# SAMD21_Pro_RF_1W.net
KiCad netlist of a schematic drawn in EAGLE
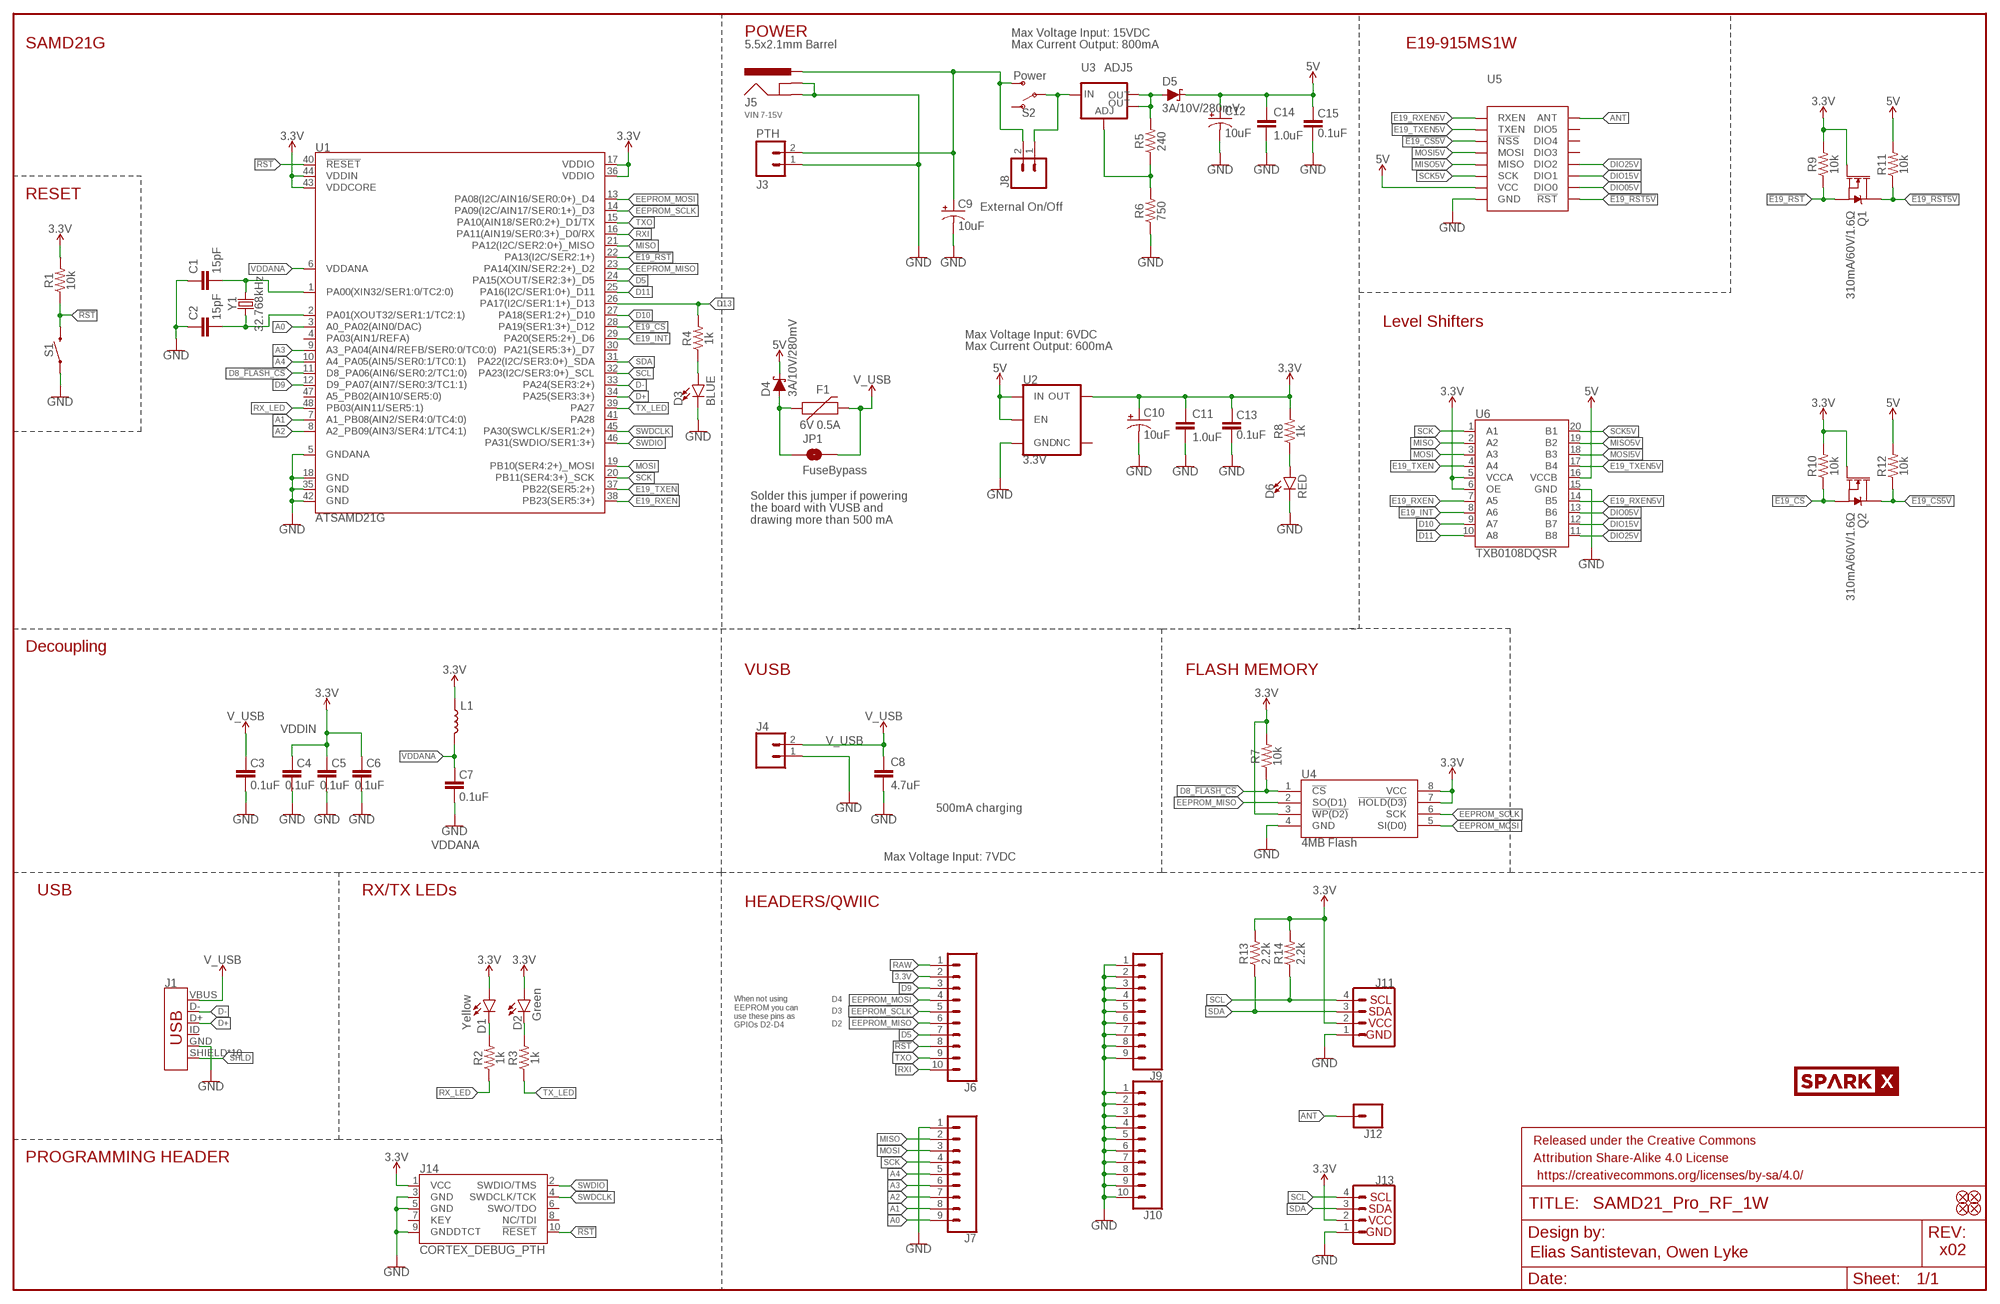
[diagram p0: schematic, sheet 1]

(export (version "E")
  (design (tool "Eeschema 10.0.6"))
  (components
    (comp (ref "C1")
      (value "15pF")
      (footprint "eagle-import:0603")
      (libsource (lib "eagle-import") (part "15PF-0603-50V-5%"))
    )
    (comp (ref "C2")
      (value "15pF")
      (footprint "eagle-import:0603")
      (libsource (lib "eagle-import") (part "15PF-0603-50V-5%"))
    )
    (comp (ref "C3")
      (value "0.1uF")
      (footprint "eagle-import:0603")
      (libsource (lib "eagle-import") (part "0.1UF-0603-25V-(+80/-20%)"))
    )
    (comp (ref "C4")
      (value "0.1uF")
      (footprint "eagle-import:0603")
      (libsource (lib "eagle-import") (part "0.1UF-0603-25V-(+80/-20%)"))
    )
    (comp (ref "C5")
      (value "0.1uF")
      (footprint "eagle-import:0603")
      (libsource (lib "eagle-import") (part "0.1UF-0603-25V-(+80/-20%)"))
    )
    (comp (ref "C6")
      (value "0.1uF")
      (footprint "eagle-import:0603")
      (libsource (lib "eagle-import") (part "0.1UF-0603-25V-(+80/-20%)"))
    )
    (comp (ref "C7")
      (value "0.1uF")
      (footprint "eagle-import:0603")
      (libsource (lib "eagle-import") (part "0.1UF-0603-25V-(+80/-20%)"))
    )
    (comp (ref "C8")
      (value "4.7uF")
      (footprint "eagle-import:0603")
      (libsource (lib "eagle-import") (part "4.7UF-0603-6.3V-(10%)"))
    )
    (comp (ref "C9")
      (value "10uF")
      (footprint "eagle-import:EIA3216")
      (libsource (lib "eagle-import") (part "10UF-POLAR-EIA3216-16V-10%(TANT)"))
    )
    (comp (ref "C10")
      (value "10uF")
      (footprint "eagle-import:EIA3216")
      (libsource (lib "eagle-import") (part "10UF-POLAR-EIA3216-16V-10%(TANT)"))
    )
    (comp (ref "C11")
      (value "1.0uF")
      (footprint "eagle-import:0603")
      (libsource (lib "eagle-import") (part "1.0UF-0603-16V-10%"))
    )
    (comp (ref "C12")
      (value "10uF")
      (footprint "eagle-import:EIA3216")
      (libsource (lib "eagle-import") (part "10UF-POLAR-EIA3216-16V-10%(TANT)"))
    )
    (comp (ref "C13")
      (value "0.1uF")
      (footprint "eagle-import:0603")
      (libsource (lib "eagle-import") (part "0.1UF-0603-25V-(+80/-20%)"))
    )
    (comp (ref "C14")
      (value "1.0uF")
      (footprint "eagle-import:0603")
      (libsource (lib "eagle-import") (part "1.0UF-0603-16V-10%"))
    )
    (comp (ref "C15")
      (value "0.1uF")
      (footprint "eagle-import:0603")
      (libsource (lib "eagle-import") (part "0.1UF-0603-25V-(+80/-20%)"))
    )
    (comp (ref "D1")
      (value "Yellow")
      (footprint "eagle-import:LED-0603")
      (libsource (lib "eagle-import") (part "LED-YELLOW0603"))
    )
    (comp (ref "D2")
      (value "Green")
      (footprint "eagle-import:LED-0603")
      (libsource (lib "eagle-import") (part "LED-GREEN0603"))
    )
    (comp (ref "D3")
      (value "BLUE")
      (footprint "eagle-import:LED-0603")
      (libsource (lib "eagle-import") (part "LED-BLUE0603"))
    )
    (comp (ref "D4")
      (value "3A/10V/280mV")
      (footprint "eagle-import:SOD-323")
      (libsource (lib "eagle-import") (part "DIODE-SCHOTTKY-BAT60A"))
    )
    (comp (ref "D5")
      (value "3A/10V/280mV")
      (footprint "eagle-import:SOD-323")
      (libsource (lib "eagle-import") (part "DIODE-SCHOTTKY-BAT60A"))
    )
    (comp (ref "D6")
      (value "RED")
      (footprint "eagle-import:LED-0603")
      (libsource (lib "eagle-import") (part "LED-RED0603"))
    )
    (comp (ref "F1")
      (value "6V 0.5A")
      (footprint "eagle-import:0805")
      (libsource (lib "eagle-import") (part "PPTC_6V500MA"))
    )
    (comp (ref "FD1")
      (value "FIDUCIAL1X2")
      (footprint "eagle-import:FIDUCIAL-1X2")
      (libsource (lib "eagle-import") (part "FIDUCIAL1X2"))
    )
    (comp (ref "FD2")
      (value "FIDUCIAL1X2")
      (footprint "eagle-import:FIDUCIAL-1X2")
      (libsource (lib "eagle-import") (part "FIDUCIAL1X2"))
    )
    (comp (ref "FD3")
      (value "FIDUCIAL1X2")
      (footprint "eagle-import:FIDUCIAL-1X2")
      (libsource (lib "eagle-import") (part "FIDUCIAL1X2"))
    )
    (comp (ref "FD4")
      (value "FIDUCIAL1X2")
      (footprint "eagle-import:FIDUCIAL-1X2")
      (libsource (lib "eagle-import") (part "FIDUCIAL1X2"))
    )
    (comp (ref "FRAME1")
      (value "FRAME-LEDGER")
      (footprint "eagle-import:CREATIVE_COMMONS")
      (libsource (lib "eagle-import") (part "FRAME-LEDGER"))
    )
    (comp (ref "J1")
      (value "USB_MICRO-B_HALF_PTH_MILL")
      (footprint "eagle-import:USB-MICROB-PTH-MILL")
      (libsource (lib "eagle-import") (part "USB_MICRO-B_HALF_PTH_MILL"))
    )
    (comp (ref "J3")
      (value "PTH")
      (footprint "eagle-import:1X02_NO_SILK")
      (libsource (lib "eagle-import") (part "CONN_021X02_NO_SILK"))
    )
    (comp (ref "J4")
      (value "CONN_021X02_NO_SILK")
      (footprint "eagle-import:1X02_NO_SILK")
      (libsource (lib "eagle-import") (part "CONN_021X02_NO_SILK"))
    )
    (comp (ref "J5")
      (value "5.5x2.1mm Barrel")
      (footprint "eagle-import:POWER_JACK_SMD")
      (libsource (lib "eagle-import") (part "POWER_JACKSMD"))
    )
    (comp (ref "J6")
      (value "CONN_10NO_SILK_PTH_FEMALE")
      (footprint "eagle-import:1X10_NO_SILK")
      (libsource (lib "eagle-import") (part "CONN_10NO_SILK_PTH_FEMALE"))
    )
    (comp (ref "J7")
      (value "CONN_09NO_SILK")
      (footprint "eagle-import:1X09_NO_SILK")
      (libsource (lib "eagle-import") (part "CONN_09NO_SILK"))
    )
    (comp (ref "J8")
      (value "External On/Off")
      (footprint "eagle-import:1X02_NO_SILK")
      (libsource (lib "eagle-import") (part "CONN_021X02_NO_SILK"))
    )
    (comp (ref "J9")
      (value "CONN_09NO_SILK")
      (footprint "eagle-import:1X09_NO_SILK")
      (libsource (lib "eagle-import") (part "CONN_09NO_SILK"))
    )
    (comp (ref "J10")
      (value "CONN_10NO_SILK_PTH_FEMALE")
      (footprint "eagle-import:1X10_NO_SILK")
      (libsource (lib "eagle-import") (part "CONN_10NO_SILK_PTH_FEMALE"))
    )
    (comp (ref "J11")
      (value "QWIIC_CONNECTORJS-1MM")
      (footprint "eagle-import:1X04_1MM_RA")
      (libsource (lib "eagle-import") (part "QWIIC_CONNECTORJS-1MM"))
    )
    (comp (ref "J12")
      (value "CONN_01PTH_NO_SILK_YES_STOP")
      (footprint "eagle-import:1X01_NO_SILK")
      (libsource (lib "eagle-import") (part "CONN_01PTH_NO_SILK_YES_STOP"))
    )
    (comp (ref "J13")
      (value "QWIIC_CONNECTORJS-1MM")
      (footprint "eagle-import:1X04_1MM_RA")
      (libsource (lib "eagle-import") (part "QWIIC_CONNECTORJS-1MM"))
    )
    (comp (ref "J14")
      (value "CORTEX_DEBUG_PTH")
      (footprint "eagle-import:2X5-PTH-1.27MM")
      (libsource (lib "eagle-import") (part "CORTEX_DEBUG_PTH"))
    )
    (comp (ref "JP1")
      (value "FuseBypass")
      (footprint "eagle-import:SMT-JUMPER_2_NO_SILK")
      (libsource (lib "eagle-import") (part "JUMPER-SMT_2_NO_SILK"))
    )
    (comp (ref "L1")
      (value "INDUCTORFB-30OHM")
      (footprint "eagle-import:0603")
      (libsource (lib "eagle-import") (part "INDUCTORFB-30OHM"))
    )
    (comp (ref "Q1")
      (value "310mA/60V/1.6Ω")
      (footprint "eagle-import:SOT323")
      (libsource (lib "eagle-import") (part "MOSFET-NCH-2N7002PW"))
    )
    (comp (ref "Q2")
      (value "310mA/60V/1.6Ω")
      (footprint "eagle-import:SOT323")
      (libsource (lib "eagle-import") (part "MOSFET-NCH-2N7002PW"))
    )
    (comp (ref "R1")
      (value "10k")
      (footprint "eagle-import:0603")
      (libsource (lib "eagle-import") (part "10KOHM-0603-1/10W-1%"))
    )
    (comp (ref "R2")
      (value "1k")
      (footprint "eagle-import:0603")
      (libsource (lib "eagle-import") (part "1KOHM-0603-1/10W-1%"))
    )
    (comp (ref "R3")
      (value "1k")
      (footprint "eagle-import:0603")
      (libsource (lib "eagle-import") (part "1KOHM-0603-1/10W-1%"))
    )
    (comp (ref "R4")
      (value "1k")
      (footprint "eagle-import:0603")
      (libsource (lib "eagle-import") (part "1KOHM-0603-1/10W-1%"))
    )
    (comp (ref "R5")
      (value "240")
      (footprint "eagle-import:0603")
      (libsource (lib "eagle-import") (part "240OHM-0603-1/10W-1%"))
    )
    (comp (ref "R6")
      (value "750")
      (footprint "eagle-import:0603")
      (libsource (lib "eagle-import") (part "750OHM-0603-1/10W-1%"))
    )
    (comp (ref "R7")
      (value "10k")
      (footprint "eagle-import:0603")
      (libsource (lib "eagle-import") (part "10KOHM-0603-1/10W-1%"))
    )
    (comp (ref "R8")
      (value "1k")
      (footprint "eagle-import:0603")
      (libsource (lib "eagle-import") (part "1KOHM-0603-1/10W-1%"))
    )
    (comp (ref "R9")
      (value "10k")
      (footprint "eagle-import:0603")
      (libsource (lib "eagle-import") (part "10KOHM-0603-1/10W-1%"))
    )
    (comp (ref "R10")
      (value "10k")
      (footprint "eagle-import:0603")
      (libsource (lib "eagle-import") (part "10KOHM-0603-1/10W-1%"))
    )
    (comp (ref "R11")
      (value "10k")
      (footprint "eagle-import:0603")
      (libsource (lib "eagle-import") (part "10KOHM-0603-1/10W-1%"))
    )
    (comp (ref "R12")
      (value "10k")
      (footprint "eagle-import:0603")
      (libsource (lib "eagle-import") (part "10KOHM-0603-1/10W-1%"))
    )
    (comp (ref "R13")
      (value "2.2k")
      (footprint "eagle-import:0603")
      (libsource (lib "eagle-import") (part "2.2KOHM-0603-1/10W-1%"))
    )
    (comp (ref "R14")
      (value "2.2k")
      (footprint "eagle-import:0603")
      (libsource (lib "eagle-import") (part "2.2KOHM-0603-1/10W-1%"))
    )
    (comp (ref "S1")
      (value "MOMENTARY-SWITCH-SPST-SMD-5.2-REDUNDANT")
      (footprint "eagle-import:TACTILE_SWITCH_SMD_5.2MM")
      (libsource (lib "eagle-import") (part "MOMENTARY-SWITCH-SPST-SMD-5.2-REDUNDANT"))
    )
    (comp (ref "S2")
      (value "Power")
      (footprint "eagle-import:SWITCH_SPST_SMD_A")
      (libsource (lib "eagle-import") (part "SWITCH-SPDT-SMD-RIGHT-ANGLE"))
    )
    (comp (ref "U$34")
      (value "SPARKX-LOGO4")
      (footprint "eagle-import:SPARKX-MEDIUM")
      (libsource (lib "eagle-import") (part "SPARKX-LOGO4"))
    )
    (comp (ref "U1")
      (value "ATSAMD21G")
      (footprint "eagle-import:QFN-48_NO_EXPOSED_PAD")
      (libsource (lib "eagle-import") (part "ATSAMD21G"))
    )
    (comp (ref "U2")
      (value "3.3V")
      (footprint "eagle-import:SOT23-5")
      (libsource (lib "eagle-import") (part "V_REG_AP2112K-3.3V"))
    )
    (comp (ref "U3")
      (value "ADJ5")
      (footprint "eagle-import:SOT223")
      (libsource (lib "eagle-import") (part "V_REG_LM1117SOT223"))
    )
    (comp (ref "U4")
      (value "4MB Flash")
      (footprint "eagle-import:SO08")
      (libsource (lib "eagle-import") (part "AT25SF041"))
    )
    (comp (ref "U5")
      (value "E19-915MS1W")
      (footprint "eagle-import:E19-915MS1W")
      (libsource (lib "eagle-import") (part "E19-915MS1W"))
    )
    (comp (ref "U6")
      (value "TXB0108DQSR")
      (footprint "eagle-import:UFDFN-20")
      (libsource (lib "eagle-import") (part "TXB0108"))
    )
    (comp (ref "Y1")
      (value "32.768kHz")
      (footprint "eagle-import:CRYSTAL-SMD-3.2X1.5MM")
      (libsource (lib "eagle-import") (part "CRYSTAL-32.768KHZSMD-3.2X1.5"))
    )
  )
  (nets
    (net (code "1") (name "/D8_~{FLASH_CS}") (class "Default")
      (node (ref "R7") (pin "1") (pinfunction "1_1") (pintype "passive"))
      (node (ref "U1") (pin "11") (pinfunction "D8_PA06(AIN6/SER0:2/TC1:0)_11") (pintype "bidirectional"))
      (node (ref "U4") (pin "1") (pinfunction "~{CS}_1") (pintype "bidirectional"))
    )
    (net (code "2") (name "/~{E19_CS5V}") (class "Default")
      (node (ref "Q2") (pin "3") (pinfunction "D_3") (pintype "bidirectional"))
      (node (ref "R12") (pin "1") (pinfunction "1_1") (pintype "passive"))
      (node (ref "U5") (pin "P$15") (pinfunction "~{NSS}_P$15") (pintype "bidirectional"))
    )
    (net (code "3") (name "/~{E19_CS}") (class "Default")
      (node (ref "Q2") (pin "2") (pinfunction "S_2") (pintype "bidirectional"))
      (node (ref "R10") (pin "1") (pinfunction "1_1") (pintype "passive"))
      (node (ref "U1") (pin "28") (pinfunction "PA19(SER1:3+)_D12_28") (pintype "bidirectional"))
    )
    (net (code "4") (name "/~{E19_RST5V}") (class "Default")
      (node (ref "Q1") (pin "3") (pinfunction "D_3") (pintype "bidirectional"))
      (node (ref "R11") (pin "1") (pinfunction "1_1") (pintype "passive"))
      (node (ref "U5") (pin "P$8") (pinfunction "~{RST}_P$8") (pintype "bidirectional"))
    )
    (net (code "5") (name "/~{E19_RST}") (class "Default")
      (node (ref "Q1") (pin "2") (pinfunction "S_2") (pintype "bidirectional"))
      (node (ref "R9") (pin "1") (pinfunction "1_1") (pintype "passive"))
      (node (ref "U1") (pin "22") (pinfunction "PA13(I2C/SER2:1+)_22") (pintype "bidirectional"))
    )
    (net (code "6") (name "/~{RST}") (class "Default")
      (node (ref "J14") (pin "10") (pinfunction "~{RESET}_10") (pintype "bidirectional"))
      (node (ref "J6") (pin "8") (pinfunction "8_8") (pintype "passive"))
      (node (ref "R1") (pin "1") (pinfunction "1_1") (pintype "passive"))
      (node (ref "S1") (pin "3") (pinfunction "2_3") (pintype "passive"))
      (node (ref "S1") (pin "4") (pinfunction "2_4") (pintype "passive"))
      (node (ref "U1") (pin "40") (pinfunction "~{RESET}_40") (pintype "bidirectional"))
    )
    (net (code "7") (name "3.3V") (class "Default")
      (node (ref "C10") (pin "+") (pinfunction "+_+") (pintype "passive"))
      (node (ref "C11") (pin "1") (pinfunction "1_1") (pintype "passive"))
      (node (ref "C13") (pin "2") (pinfunction "2_2") (pintype "passive"))
      (node (ref "C4") (pin "2") (pinfunction "2_2") (pintype "passive"))
      (node (ref "C5") (pin "2") (pinfunction "2_2") (pintype "passive"))
      (node (ref "C6") (pin "2") (pinfunction "2_2") (pintype "passive"))
      (node (ref "D1") (pin "A") (pinfunction "A_A") (pintype "passive"))
      (node (ref "D2") (pin "A") (pinfunction "A_A") (pintype "passive"))
      (node (ref "J11") (pin "2") (pinfunction "2_2") (pintype "power_in"))
      (node (ref "J13") (pin "2") (pinfunction "2_2") (pintype "power_in"))
      (node (ref "J14") (pin "1") (pinfunction "VCC_1") (pintype "bidirectional"))
      (node (ref "J6") (pin "2") (pinfunction "2_2") (pintype "passive"))
      (node (ref "L1") (pin "1") (pinfunction "1_1") (pintype "passive"))
      (node (ref "Q1") (pin "1") (pinfunction "G_1") (pintype "bidirectional"))
      (node (ref "Q2") (pin "1") (pinfunction "G_1") (pintype "bidirectional"))
      (node (ref "R1") (pin "2") (pinfunction "2_2") (pintype "passive"))
      (node (ref "R10") (pin "2") (pinfunction "2_2") (pintype "passive"))
      (node (ref "R13") (pin "2") (pinfunction "2_2") (pintype "passive"))
      (node (ref "R14") (pin "2") (pinfunction "2_2") (pintype "passive"))
      (node (ref "R7") (pin "2") (pinfunction "2_2") (pintype "passive"))
      (node (ref "R8") (pin "2") (pinfunction "2_2") (pintype "passive"))
      (node (ref "R9") (pin "2") (pinfunction "2_2") (pintype "passive"))
      (node (ref "U1") (pin "17") (pinfunction "VDDIO_17") (pintype "bidirectional"))
      (node (ref "U1") (pin "36") (pinfunction "VDDIO_36") (pintype "bidirectional"))
      (node (ref "U1") (pin "43") (pinfunction "VDDCORE_43") (pintype "bidirectional"))
      (node (ref "U1") (pin "44") (pinfunction "VDDIN_44") (pintype "bidirectional"))
      (node (ref "U2") (pin "5") (pinfunction "OUT_5") (pintype "passive"))
      (node (ref "U4") (pin "3") (pinfunction "~{WP(D2})_3") (pintype "bidirectional"))
      (node (ref "U4") (pin "7") (pinfunction "~{HOLD(D3})_7") (pintype "bidirectional"))
      (node (ref "U4") (pin "8") (pinfunction "VCC_8") (pintype "bidirectional"))
      (node (ref "U6") (pin "5") (pinfunction "VCCA_5") (pintype "bidirectional"))
      (node (ref "U6") (pin "6") (pinfunction "OE_6") (pintype "bidirectional"))
    )
    (net (code "8") (name "5V") (class "Default")
      (node (ref "C12") (pin "+") (pinfunction "+_+") (pintype "passive"))
      (node (ref "C14") (pin "1") (pinfunction "1_1") (pintype "passive"))
      (node (ref "C15") (pin "2") (pinfunction "2_2") (pintype "passive"))
      (node (ref "D4") (pin "C") (pinfunction "C_C") (pintype "passive"))
      (node (ref "D5") (pin "C") (pinfunction "C_C") (pintype "passive"))
      (node (ref "R11") (pin "2") (pinfunction "2_2") (pintype "passive"))
      (node (ref "R12") (pin "2") (pinfunction "2_2") (pintype "passive"))
      (node (ref "U2") (pin "1") (pinfunction "IN_1") (pintype "input"))
      (node (ref "U2") (pin "3") (pinfunction "EN_3") (pintype "input"))
      (node (ref "U5") (pin "P$11") (pinfunction "VCC_P$11") (pintype "bidirectional"))
      (node (ref "U6") (pin "16") (pinfunction "VCCB_16") (pintype "bidirectional"))
    )
    (net (code "9") (name "A0") (class "Default")
      (node (ref "J7") (pin "9") (pinfunction "9_9") (pintype "passive"))
      (node (ref "U1") (pin "3") (pinfunction "A0_PA02(AIN0/DAC)_3") (pintype "bidirectional"))
    )
    (net (code "10") (name "A1") (class "Default")
      (node (ref "J7") (pin "8") (pinfunction "8_8") (pintype "passive"))
      (node (ref "U1") (pin "7") (pinfunction "A1_PB08(AIN2/SER4:0/TC4:0)_7") (pintype "bidirectional"))
    )
    (net (code "11") (name "A2") (class "Default")
      (node (ref "J7") (pin "7") (pinfunction "7_7") (pintype "passive"))
      (node (ref "U1") (pin "8") (pinfunction "A2_PB09(AIN3/SER4:1/TC4:1)_8") (pintype "bidirectional"))
    )
    (net (code "12") (name "A3") (class "Default")
      (node (ref "J7") (pin "6") (pinfunction "6_6") (pintype "passive"))
      (node (ref "U1") (pin "9") (pinfunction "A3_PA04(AIN4/REFB/SER0:0/TC0:0)_9") (pintype "bidirectional"))
    )
    (net (code "13") (name "A4") (class "Default")
      (node (ref "J7") (pin "5") (pinfunction "5_5") (pintype "passive"))
      (node (ref "U1") (pin "10") (pinfunction "A4_PA05(AIN5/SER0:1/TC0:1)_10") (pintype "bidirectional"))
    )
    (net (code "14") (name "ANT") (class "Default")
      (node (ref "J12") (pin "1") (pinfunction "1_1") (pintype "passive"))
      (node (ref "U5") (pin "P$19") (pinfunction "ANT_P$19") (pintype "bidirectional"))
    )
    (net (code "15") (name "D+") (class "Default")
      (node (ref "J1") (pin "D+") (pinfunction "D+_D+") (pintype "bidirectional"))
      (node (ref "U1") (pin "34") (pinfunction "PA25(SER3:3+)_34") (pintype "bidirectional"))
    )
    (net (code "16") (name "D-") (class "Default")
      (node (ref "J1") (pin "D-") (pinfunction "D-_D-") (pintype "bidirectional"))
      (node (ref "U1") (pin "33") (pinfunction "PA24(SER3:2+)_33") (pintype "bidirectional"))
    )
    (net (code "17") (name "D5") (class "Default")
      (node (ref "J6") (pin "7") (pinfunction "7_7") (pintype "passive"))
      (node (ref "U1") (pin "24") (pinfunction "PA15(XOUT/SER2:3+)_D5_24") (pintype "bidirectional"))
    )
    (net (code "18") (name "D9") (class "Default")
      (node (ref "J6") (pin "3") (pinfunction "3_3") (pintype "passive"))
      (node (ref "U1") (pin "12") (pinfunction "D9_PA07(AIN7/SER0:3/TC1:1)_12") (pintype "bidirectional"))
    )
    (net (code "19") (name "D10") (class "Default")
      (node (ref "U1") (pin "27") (pinfunction "PA18(SER1:2+)_D10_27") (pintype "bidirectional"))
      (node (ref "U6") (pin "9") (pinfunction "A7_9") (pintype "bidirectional"))
    )
    (net (code "20") (name "D11") (class "Default")
      (node (ref "U1") (pin "25") (pinfunction "PA16(I2C/SER1:0+)_D11_25") (pintype "bidirectional"))
      (node (ref "U6") (pin "10") (pinfunction "A8_10") (pintype "bidirectional"))
    )
    (net (code "21") (name "D13") (class "Default")
      (node (ref "R4") (pin "2") (pinfunction "2_2") (pintype "passive"))
      (node (ref "U1") (pin "26") (pinfunction "PA17(I2C/SER1:1+)_D13_26") (pintype "bidirectional"))
    )
    (net (code "22") (name "DIO05V") (class "Default")
      (node (ref "U5") (pin "P$7") (pinfunction "DIO0_P$7") (pintype "bidirectional"))
      (node (ref "U6") (pin "13") (pinfunction "B6_13") (pintype "bidirectional"))
    )
    (net (code "23") (name "DIO15V") (class "Default")
      (node (ref "U5") (pin "P$6") (pinfunction "DIO1_P$6") (pintype "bidirectional"))
      (node (ref "U6") (pin "12") (pinfunction "B7_12") (pintype "bidirectional"))
    )
    (net (code "24") (name "DIO25V") (class "Default")
      (node (ref "U5") (pin "P$5") (pinfunction "DIO2_P$5") (pintype "bidirectional"))
      (node (ref "U6") (pin "11") (pinfunction "B8_11") (pintype "bidirectional"))
    )
    (net (code "25") (name "E19_INT") (class "Default")
      (node (ref "U1") (pin "29") (pinfunction "PA20(SER5:2+)_D6_29") (pintype "bidirectional"))
      (node (ref "U6") (pin "8") (pinfunction "A6_8") (pintype "bidirectional"))
    )
    (net (code "26") (name "E19_RXEN") (class "Default")
      (node (ref "U1") (pin "38") (pinfunction "PB23(SER5:3+)_38") (pintype "bidirectional"))
      (node (ref "U6") (pin "7") (pinfunction "A5_7") (pintype "bidirectional"))
    )
    (net (code "27") (name "E19_RXEN5V") (class "Default")
      (node (ref "U5") (pin "P$17") (pinfunction "RXEN_P$17") (pintype "bidirectional"))
      (node (ref "U6") (pin "14") (pinfunction "B5_14") (pintype "bidirectional"))
    )
    (net (code "28") (name "E19_TXEN") (class "Default")
      (node (ref "U1") (pin "37") (pinfunction "PB22(SER5:2+)_37") (pintype "bidirectional"))
      (node (ref "U6") (pin "4") (pinfunction "A4_4") (pintype "bidirectional"))
    )
    (net (code "29") (name "E19_TXEN5V") (class "Default")
      (node (ref "U5") (pin "P$16") (pinfunction "TXEN_P$16") (pintype "bidirectional"))
      (node (ref "U6") (pin "17") (pinfunction "B4_17") (pintype "bidirectional"))
    )
    (net (code "30") (name "EEPROM_MISO") (class "Default")
      (node (ref "J6") (pin "6") (pinfunction "6_6") (pintype "passive"))
      (node (ref "U1") (pin "23") (pinfunction "PA14(XIN/SER2:2+)_D2_23") (pintype "bidirectional"))
      (node (ref "U4") (pin "2") (pinfunction "SO(D1)_2") (pintype "bidirectional"))
    )
    (net (code "31") (name "EEPROM_MOSI") (class "Default")
      (node (ref "J6") (pin "4") (pinfunction "4_4") (pintype "passive"))
      (node (ref "U1") (pin "13") (pinfunction "PA08(I2C/AIN16/SER0:0+)_D4_13") (pintype "bidirectional"))
      (node (ref "U4") (pin "5") (pinfunction "SI(D0)_5") (pintype "bidirectional"))
    )
    (net (code "32") (name "EEPROM_SCLK") (class "Default")
      (node (ref "J6") (pin "5") (pinfunction "5_5") (pintype "passive"))
      (node (ref "U1") (pin "14") (pinfunction "PA09(I2C/AIN17/SER0:1+)_D3_14") (pintype "bidirectional"))
      (node (ref "U4") (pin "6") (pinfunction "SCK_6") (pintype "bidirectional"))
    )
    (net (code "33") (name "GND") (class "Default")
      (node (ref "C1") (pin "1") (pinfunction "1_1") (pintype "passive"))
      (node (ref "C10") (pin "-") (pinfunction "-_-") (pintype "passive"))
      (node (ref "C11") (pin "2") (pinfunction "2_2") (pintype "passive"))
      (node (ref "C12") (pin "-") (pinfunction "-_-") (pintype "passive"))
      (node (ref "C13") (pin "1") (pinfunction "1_1") (pintype "passive"))
      (node (ref "C14") (pin "2") (pinfunction "2_2") (pintype "passive"))
      (node (ref "C15") (pin "1") (pinfunction "1_1") (pintype "passive"))
      (node (ref "C2") (pin "1") (pinfunction "1_1") (pintype "passive"))
      (node (ref "C3") (pin "1") (pinfunction "1_1") (pintype "passive"))
      (node (ref "C4") (pin "1") (pinfunction "1_1") (pintype "passive"))
      (node (ref "C5") (pin "1") (pinfunction "1_1") (pintype "passive"))
      (node (ref "C6") (pin "1") (pinfunction "1_1") (pintype "passive"))
      (node (ref "C7") (pin "1") (pinfunction "1_1") (pintype "passive"))
      (node (ref "C8") (pin "2") (pinfunction "2_2") (pintype "passive"))
      (node (ref "C9") (pin "-") (pinfunction "-_-") (pintype "passive"))
      (node (ref "D3") (pin "C") (pinfunction "C_C") (pintype "passive"))
      (node (ref "D6") (pin "C") (pinfunction "C_C") (pintype "passive"))
      (node (ref "J1") (pin "GND") (pinfunction "GND_GND") (pintype "power_in"))
      (node (ref "J10") (pin "1") (pinfunction "1_1") (pintype "passive"))
      (node (ref "J10") (pin "10") (pinfunction "10_10") (pintype "passive"))
      (node (ref "J10") (pin "2") (pinfunction "2_2") (pintype "passive"))
      (node (ref "J10") (pin "3") (pinfunction "3_3") (pintype "passive"))
      (node (ref "J10") (pin "4") (pinfunction "4_4") (pintype "passive"))
      (node (ref "J10") (pin "5") (pinfunction "5_5") (pintype "passive"))
      (node (ref "J10") (pin "6") (pinfunction "6_6") (pintype "passive"))
      (node (ref "J10") (pin "7") (pinfunction "7_7") (pintype "passive"))
      (node (ref "J10") (pin "8") (pinfunction "8_8") (pintype "passive"))
      (node (ref "J10") (pin "9") (pinfunction "9_9") (pintype "passive"))
      (node (ref "J11") (pin "1") (pinfunction "1_1") (pintype "power_in"))
      (node (ref "J13") (pin "1") (pinfunction "1_1") (pintype "power_in"))
      (node (ref "J14") (pin "3") (pinfunction "GND_3") (pintype "bidirectional"))
      (node (ref "J14") (pin "5") (pinfunction "GND_5") (pintype "bidirectional"))
      (node (ref "J14") (pin "9") (pinfunction "GNDDTCT_9") (pintype "bidirectional"))
      (node (ref "J3") (pin "1") (pinfunction "1_1") (pintype "passive"))
      (node (ref "J4") (pin "1") (pinfunction "1_1") (pintype "passive"))
      (node (ref "J5") (pin "GND") (pinfunction "GNDBREAK_GND") (pintype "bidirectional"))
      (node (ref "J5") (pin "P$4") (pinfunction "GND_P$4") (pintype "bidirectional"))
      (node (ref "J7") (pin "1") (pinfunction "1_1") (pintype "passive"))
      (node (ref "J9") (pin "1") (pinfunction "1_1") (pintype "passive"))
      (node (ref "J9") (pin "2") (pinfunction "2_2") (pintype "passive"))
      (node (ref "J9") (pin "3") (pinfunction "3_3") (pintype "passive"))
      (node (ref "J9") (pin "4") (pinfunction "4_4") (pintype "passive"))
      (node (ref "J9") (pin "5") (pinfunction "5_5") (pintype "passive"))
      (node (ref "J9") (pin "6") (pinfunction "6_6") (pintype "passive"))
      (node (ref "J9") (pin "7") (pinfunction "7_7") (pintype "passive"))
      (node (ref "J9") (pin "8") (pinfunction "8_8") (pintype "passive"))
      (node (ref "J9") (pin "9") (pinfunction "9_9") (pintype "passive"))
      (node (ref "R6") (pin "1") (pinfunction "1_1") (pintype "passive"))
      (node (ref "S1") (pin "1") (pinfunction "1_1") (pintype "passive"))
      (node (ref "S1") (pin "2") (pinfunction "1_2") (pintype "passive"))
      (node (ref "U1") (pin "18") (pinfunction "GND_18") (pintype "bidirectional"))
      (node (ref "U1") (pin "35") (pinfunction "GND_35") (pintype "bidirectional"))
      (node (ref "U1") (pin "42") (pinfunction "GND_42") (pintype "bidirectional"))
      (node (ref "U1") (pin "5") (pinfunction "GNDANA_5") (pintype "bidirectional"))
      (node (ref "U2") (pin "2") (pinfunction "GND_2") (pintype "input"))
      (node (ref "U4") (pin "4") (pinfunction "GND_4") (pintype "bidirectional"))
      (node (ref "U5") (pin "P$1") (pinfunction "GND_P$1") (pintype "bidirectional"))
      (node (ref "U5") (pin "P$10") (pinfunction "GND_P$10") (pintype "bidirectional"))
      (node (ref "U5") (pin "P$18") (pinfunction "GND_P$18") (pintype "bidirectional"))
      (node (ref "U5") (pin "P$20") (pinfunction "GND_P$20") (pintype "bidirectional"))
      (node (ref "U5") (pin "P$21") (pinfunction "GND_P$21") (pintype "bidirectional"))
      (node (ref "U5") (pin "P$22") (pinfunction "GND_P$22") (pintype "bidirectional"))
      (node (ref "U5") (pin "P$9") (pinfunction "GND_P$9") (pintype "bidirectional"))
      (node (ref "U6") (pin "15") (pinfunction "GND_15") (pintype "bidirectional"))
    )
    (net (code "34") (name "MISO") (class "Default")
      (node (ref "J7") (pin "2") (pinfunction "2_2") (pintype "passive"))
      (node (ref "U1") (pin "21") (pinfunction "PA12(I2C/SER2:0+)_MISO_21") (pintype "bidirectional"))
      (node (ref "U6") (pin "2") (pinfunction "A2_2") (pintype "bidirectional"))
    )
    (net (code "35") (name "MISO5V") (class "Default")
      (node (ref "U5") (pin "P$13") (pinfunction "MISO_P$13") (pintype "bidirectional"))
      (node (ref "U6") (pin "19") (pinfunction "B2_19") (pintype "bidirectional"))
    )
    (net (code "36") (name "MOSI") (class "Default")
      (node (ref "J7") (pin "3") (pinfunction "3_3") (pintype "passive"))
      (node (ref "U1") (pin "19") (pinfunction "PB10(SER4:2+)_MOSI_19") (pintype "bidirectional"))
      (node (ref "U6") (pin "3") (pinfunction "A3_3") (pintype "bidirectional"))
    )
    (net (code "37") (name "MOSI5V") (class "Default")
      (node (ref "U5") (pin "P$14") (pinfunction "MOSI_P$14") (pintype "bidirectional"))
      (node (ref "U6") (pin "18") (pinfunction "B3_18") (pintype "bidirectional"))
    )
    (net (code "38") (name "Net-(D1-PadC)") (class "Default")
      (node (ref "D1") (pin "C") (pinfunction "C_C") (pintype "passive"))
      (node (ref "R2") (pin "2") (pinfunction "2_2") (pintype "passive"))
    )
    (net (code "39") (name "Net-(D2-PadC)") (class "Default")
      (node (ref "D2") (pin "C") (pinfunction "C_C") (pintype "passive"))
      (node (ref "R3") (pin "2") (pinfunction "2_2") (pintype "passive"))
    )
    (net (code "40") (name "Net-(D3-PadA)") (class "Default")
      (node (ref "D3") (pin "A") (pinfunction "A_A") (pintype "passive"))
      (node (ref "R4") (pin "1") (pinfunction "1_1") (pintype "passive"))
    )
    (net (code "41") (name "Net-(D4-PadA)") (class "Default")
      (node (ref "D4") (pin "A") (pinfunction "A_A") (pintype "passive"))
      (node (ref "F1") (pin "1") (pinfunction "1_1") (pintype "bidirectional"))
      (node (ref "JP1") (pin "1") (pinfunction "1_1") (pintype "passive"))
    )
    (net (code "42") (name "Net-(D5-PadA)") (class "Default")
      (node (ref "D5") (pin "A") (pinfunction "A_A") (pintype "passive"))
      (node (ref "R5") (pin "2") (pinfunction "2_2") (pintype "passive"))
      (node (ref "U3") (pin "2") (pinfunction "OUT_2") (pintype "output"))
      (node (ref "U3") (pin "4") (pinfunction "OUT_4") (pintype "output"))
    )
    (net (code "43") (name "Net-(D6-PadA)") (class "Default")
      (node (ref "D6") (pin "A") (pinfunction "A_A") (pintype "passive"))
      (node (ref "R8") (pin "1") (pinfunction "1_1") (pintype "passive"))
    )
    (net (code "44") (name "Net-(J5-PWR)") (class "Default")
      (node (ref "C9") (pin "+") (pinfunction "+_+") (pintype "passive"))
      (node (ref "J3") (pin "2") (pinfunction "2_2") (pintype "passive"))
      (node (ref "J5") (pin "VIN0") (pinfunction "PWR_VIN0") (pintype "bidirectional"))
      (node (ref "J8") (pin "2") (pinfunction "2_2") (pintype "passive"))
      (node (ref "S2") (pin "3") (pinfunction "S_3") (pintype "passive"))
    )
    (net (code "45") (name "Net-(U1-PA00(XIN32{slash}SER1:0{slash}TC2:0))") (class "Default")
      (node (ref "C1") (pin "2") (pinfunction "2_2") (pintype "passive"))
      (node (ref "U1") (pin "1") (pinfunction "PA00(XIN32/SER1:0/TC2:0)_1") (pintype "bidirectional"))
      (node (ref "Y1") (pin "P$2") (pinfunction "2_P$2") (pintype "passive"))
    )
    (net (code "46") (name "Net-(U1-PA01(XOUT32{slash}SER1:1{slash}TC2:1))") (class "Default")
      (node (ref "C2") (pin "2") (pinfunction "2_2") (pintype "passive"))
      (node (ref "U1") (pin "2") (pinfunction "PA01(XOUT32/SER1:1/TC2:1)_2") (pintype "bidirectional"))
      (node (ref "Y1") (pin "P$1") (pinfunction "1_P$1") (pintype "passive"))
    )
    (net (code "47") (name "Net-(U3-ADJ)") (class "Default")
      (node (ref "R5") (pin "1") (pinfunction "1_1") (pintype "passive"))
      (node (ref "R6") (pin "2") (pinfunction "2_2") (pintype "passive"))
      (node (ref "U3") (pin "1") (pinfunction "ADJ_1") (pintype "input"))
    )
    (net (code "48") (name "RAW") (class "Default")
      (node (ref "J6") (pin "1") (pinfunction "1_1") (pintype "passive"))
      (node (ref "J8") (pin "1") (pinfunction "1_1") (pintype "passive"))
      (node (ref "S2") (pin "2") (pinfunction "P_2") (pintype "passive"))
      (node (ref "U3") (pin "3") (pinfunction "IN_3") (pintype "input"))
    )
    (net (code "49") (name "RXI") (class "Default")
      (node (ref "J6") (pin "10") (pinfunction "10_10") (pintype "passive"))
      (node (ref "U1") (pin "16") (pinfunction "PA11(AIN19/SER0:3+)_D0/RX_16") (pintype "bidirectional"))
    )
    (net (code "50") (name "RX_LED") (class "Default")
      (node (ref "R2") (pin "1") (pinfunction "1_1") (pintype "passive"))
      (node (ref "U1") (pin "48") (pinfunction "PB03(AIN11/SER5:1)_48") (pintype "bidirectional"))
    )
    (net (code "51") (name "SCK") (class "Default")
      (node (ref "J7") (pin "4") (pinfunction "4_4") (pintype "passive"))
      (node (ref "U1") (pin "20") (pinfunction "PB11(SER4:3+)_SCK_20") (pintype "bidirectional"))
      (node (ref "U6") (pin "1") (pinfunction "A1_1") (pintype "bidirectional"))
    )
    (net (code "52") (name "SCK5V") (class "Default")
      (node (ref "U5") (pin "P$12") (pinfunction "SCK_P$12") (pintype "bidirectional"))
      (node (ref "U6") (pin "20") (pinfunction "B1_20") (pintype "bidirectional"))
    )
    (net (code "53") (name "SCL") (class "Default")
      (node (ref "J11") (pin "4") (pinfunction "4_4") (pintype "passive"))
      (node (ref "J13") (pin "4") (pinfunction "4_4") (pintype "passive"))
      (node (ref "R14") (pin "1") (pinfunction "1_1") (pintype "passive"))
      (node (ref "U1") (pin "32") (pinfunction "PA23(I2C/SER3:0+)_SCL_32") (pintype "bidirectional"))
    )
    (net (code "54") (name "SDA") (class "Default")
      (node (ref "J11") (pin "3") (pinfunction "3_3") (pintype "passive"))
      (node (ref "J13") (pin "3") (pinfunction "3_3") (pintype "passive"))
      (node (ref "R13") (pin "1") (pinfunction "1_1") (pintype "passive"))
      (node (ref "U1") (pin "31") (pinfunction "PA22(I2C/SER3:0+)_SDA_31") (pintype "bidirectional"))
    )
    (net (code "55") (name "SHLD") (class "Default")
      (node (ref "J1") (pin "SHIELD") (pinfunction "SHIELD_SHIELD") (pintype "bidirectional"))
      (node (ref "J1") (pin "SHIELD10") (pinfunction "SHIELD_SHIELD10") (pintype "bidirectional"))
      (node (ref "J1") (pin "SHIELD2") (pinfunction "SHIELD_SHIELD2") (pintype "bidirectional"))
      (node (ref "J1") (pin "SHIELD3") (pinfunction "SHIELD_SHIELD3") (pintype "bidirectional"))
      (node (ref "J1") (pin "SHIELD4") (pinfunction "SHIELD_SHIELD4") (pintype "bidirectional"))
      (node (ref "J1") (pin "SHIELD5") (pinfunction "SHIELD_SHIELD5") (pintype "bidirectional"))
      (node (ref "J1") (pin "SHIELD6") (pinfunction "SHIELD_SHIELD6") (pintype "bidirectional"))
      (node (ref "J1") (pin "SHIELD7") (pinfunction "SHIELD_SHIELD7") (pintype "bidirectional"))
      (node (ref "J1") (pin "SHIELD8") (pinfunction "SHIELD_SHIELD8") (pintype "bidirectional"))
      (node (ref "J1") (pin "SHIELD9") (pinfunction "SHIELD_SHIELD9") (pintype "bidirectional"))
    )
    (net (code "56") (name "SWDCLK") (class "Default")
      (node (ref "J14") (pin "4") (pinfunction "SWDCLK/TCK_4") (pintype "bidirectional"))
      (node (ref "U1") (pin "45") (pinfunction "PA30(SWCLK/SER1:2+)_45") (pintype "bidirectional"))
    )
    (net (code "57") (name "SWDIO") (class "Default")
      (node (ref "J14") (pin "2") (pinfunction "SWDIO/TMS_2") (pintype "bidirectional"))
      (node (ref "U1") (pin "46") (pinfunction "PA31(SWDIO/SER1:3+)_46") (pintype "bidirectional"))
    )
    (net (code "58") (name "TXO") (class "Default")
      (node (ref "J6") (pin "9") (pinfunction "9_9") (pintype "passive"))
      (node (ref "U1") (pin "15") (pinfunction "PA10(AIN18/SER0:2+)_D1/TX_15") (pintype "bidirectional"))
    )
    (net (code "59") (name "TX_LED") (class "Default")
      (node (ref "R3") (pin "1") (pinfunction "1_1") (pintype "passive"))
      (node (ref "U1") (pin "39") (pinfunction "PA27_39") (pintype "bidirectional"))
    )
    (net (code "60") (name "VDDANA") (class "Default")
      (node (ref "C7") (pin "2") (pinfunction "2_2") (pintype "passive"))
      (node (ref "L1") (pin "2") (pinfunction "2_2") (pintype "passive"))
      (node (ref "U1") (pin "6") (pinfunction "VDDANA_6") (pintype "bidirectional"))
    )
    (net (code "61") (name "V_USB") (class "Default")
      (node (ref "C3") (pin "2") (pinfunction "2_2") (pintype "passive"))
      (node (ref "C8") (pin "1") (pinfunction "1_1") (pintype "passive"))
      (node (ref "F1") (pin "2") (pinfunction "2_2") (pintype "bidirectional"))
      (node (ref "J1") (pin "VBUS") (pinfunction "VBUS_VBUS") (pintype "power_in"))
      (node (ref "J4") (pin "2") (pinfunction "2_2") (pintype "passive"))
      (node (ref "JP1") (pin "2") (pinfunction "2_2") (pintype "passive"))
    )
    (net (code "62") (name "unconnected-(J1-PadID)") (class "Default")
      (node (ref "J1") (pin "ID") (pinfunction "ID_ID") (pintype "bidirectional"))
    )
    (net (code "63") (name "unconnected-(J14-KEY-Pad7)") (class "Default")
      (node (ref "J14") (pin "7") (pinfunction "KEY_7") (pintype "bidirectional"))
    )
    (net (code "64") (name "unconnected-(J14-NC{slash}TDI-Pad8)") (class "Default")
      (node (ref "J14") (pin "8") (pinfunction "NC/TDI_8") (pintype "bidirectional"))
    )
    (net (code "65") (name "unconnected-(J14-SWO{slash}TDO-Pad6)") (class "Default")
      (node (ref "J14") (pin "6") (pinfunction "SWO/TDO_6") (pintype "bidirectional"))
    )
    (net (code "66") (name "unconnected-(S2-O-Pad1)") (class "Default")
      (node (ref "S2") (pin "1") (pinfunction "O_1") (pintype "passive"))
    )
    (net (code "67") (name "unconnected-(U1-A5_PB02(AIN10{slash}SER5:0)-Pad47)") (class "Default")
      (node (ref "U1") (pin "47") (pinfunction "A5_PB02(AIN10/SER5:0)_47") (pintype "bidirectional"))
    )
    (net (code "68") (name "unconnected-(U1-PA03(AIN1{slash}REFA)-Pad4)") (class "Default")
      (node (ref "U1") (pin "4") (pinfunction "PA03(AIN1/REFA)_4") (pintype "bidirectional"))
    )
    (net (code "69") (name "unconnected-(U1-PA21(SER5:3+)_D7-Pad30)") (class "Default")
      (node (ref "U1") (pin "30") (pinfunction "PA21(SER5:3+)_D7_30") (pintype "bidirectional"))
    )
    (net (code "70") (name "unconnected-(U1-PA28-Pad41)") (class "Default")
      (node (ref "U1") (pin "41") (pinfunction "PA28_41") (pintype "bidirectional"))
    )
    (net (code "71") (name "unconnected-(U2-NC-Pad4)") (class "Default")
      (node (ref "U2") (pin "4") (pinfunction "NC_4") (pintype "no_connect"))
    )
    (net (code "72") (name "unconnected-(U5-DIO3-PadP$4)") (class "Default")
      (node (ref "U5") (pin "P$4") (pinfunction "DIO3_P$4") (pintype "bidirectional"))
    )
    (net (code "73") (name "unconnected-(U5-DIO4-PadP$3)") (class "Default")
      (node (ref "U5") (pin "P$3") (pinfunction "DIO4_P$3") (pintype "bidirectional"))
    )
    (net (code "74") (name "unconnected-(U5-DIO5-PadP$2)") (class "Default")
      (node (ref "U5") (pin "P$2") (pinfunction "DIO5_P$2") (pintype "bidirectional"))
    )
  )
)
